# ts5.net
KiCad netlist of a schematic drawn in EAGLE
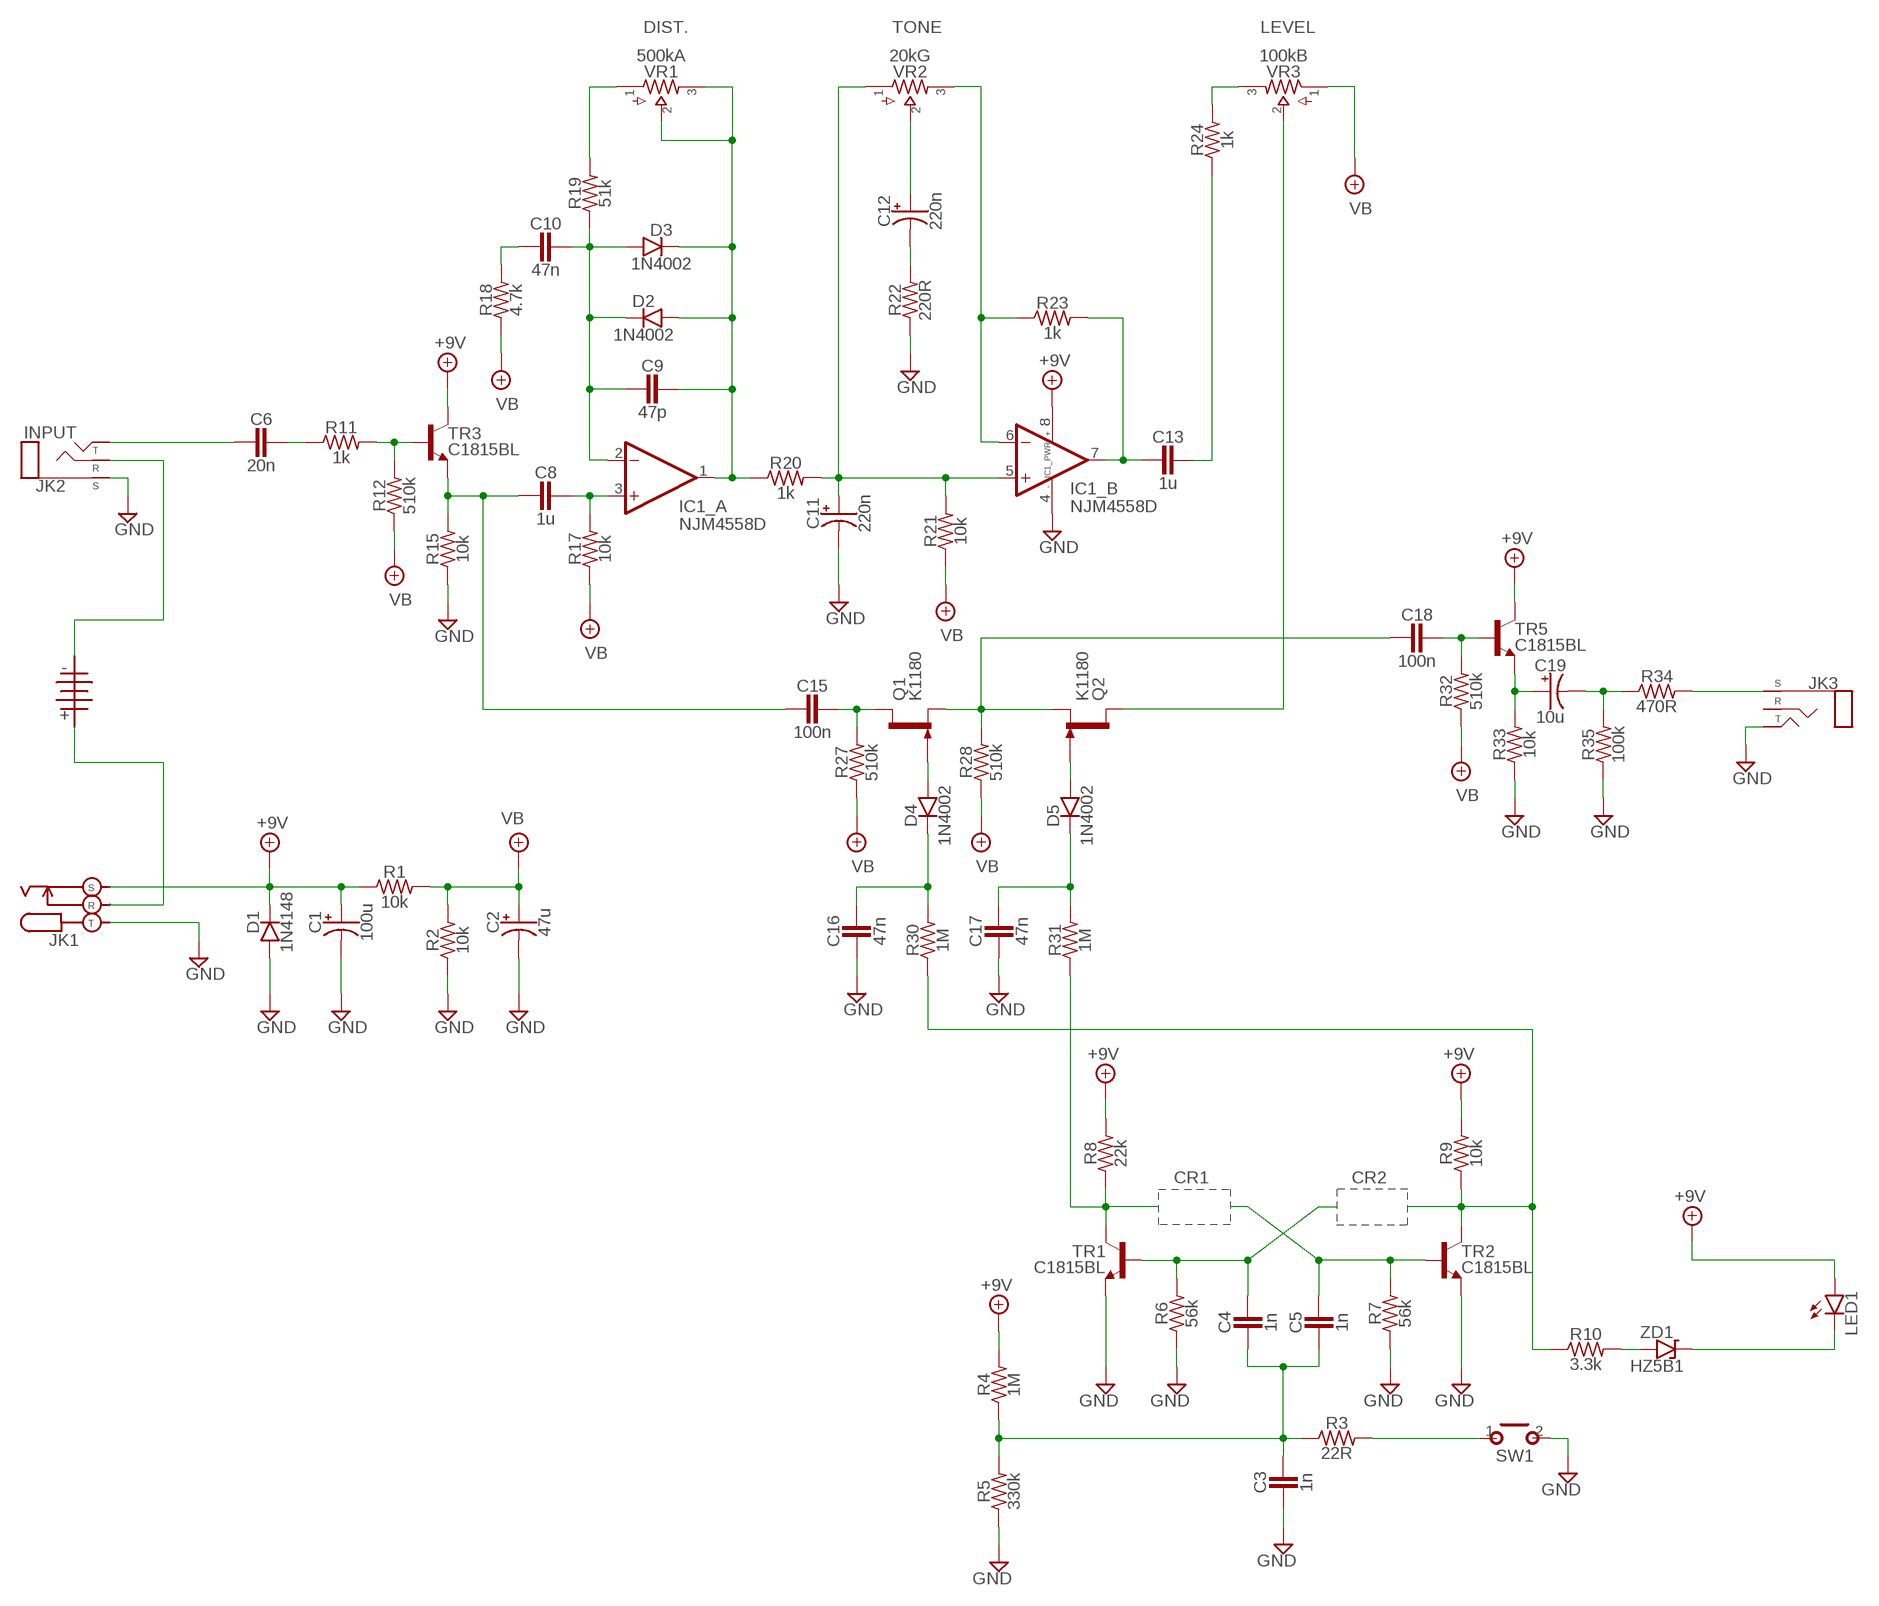
[diagram p0: schematic, sheet 1]

(export (version "E")
  (design (tool "Eeschema 10.0.6"))
  (components
    (comp (ref "1101")
      (value "BATTERY")
      (footprint "eagle-import:TWO_PADS")
      (libsource (lib "eagle-import") (part "BATTERY"))
    )
    (comp (ref "C1")
      (value "100u")
      (footprint "eagle-import:050_020")
      (libsource (lib "eagle-import") (part "0500"))
    )
    (comp (ref "C2")
      (value "47u")
      (footprint "eagle-import:050_020")
      (libsource (lib "eagle-import") (part "0500"))
    )
    (comp (ref "C3")
      (value "1n")
      (footprint "eagle-import:BOX_SMALL")
      (libsource (lib "eagle-import") (part "CER/FILMBOX.1"))
    )
    (comp (ref "C4")
      (value "1n")
      (footprint "eagle-import:BOX_SMALL")
      (libsource (lib "eagle-import") (part "CER/FILMBOX.1"))
    )
    (comp (ref "C5")
      (value "1n")
      (footprint "eagle-import:BOX_SMALL")
      (libsource (lib "eagle-import") (part "CER/FILMBOX.1"))
    )
    (comp (ref "C6")
      (value "20n")
      (footprint "eagle-import:BOX_SMALL")
      (libsource (lib "eagle-import") (part "CER/FILMBOX.1"))
    )
    (comp (ref "C8")
      (value "1u")
      (footprint "eagle-import:BOX_SMALL")
      (libsource (lib "eagle-import") (part "CER/FILMBOX.1"))
    )
    (comp (ref "C9")
      (value "47p")
      (footprint "eagle-import:BOX_SMALL")
      (libsource (lib "eagle-import") (part "CER/FILMBOX.1"))
    )
    (comp (ref "C10")
      (value "47n")
      (footprint "eagle-import:BOX_SMALL")
      (libsource (lib "eagle-import") (part "CER/FILMBOX.1"))
    )
    (comp (ref "C11")
      (value "220n")
      (footprint "eagle-import:050_020")
      (libsource (lib "eagle-import") (part "0500"))
    )
    (comp (ref "C12")
      (value "220n")
      (footprint "eagle-import:050_020")
      (libsource (lib "eagle-import") (part "0500"))
    )
    (comp (ref "C13")
      (value "1u")
      (footprint "eagle-import:BOX_SMALL")
      (libsource (lib "eagle-import") (part "CER/FILMBOX.1"))
    )
    (comp (ref "C15")
      (value "100n")
      (footprint "eagle-import:BOX_SMALL")
      (libsource (lib "eagle-import") (part "CER/FILMBOX.1"))
    )
    (comp (ref "C16")
      (value "47n")
      (footprint "eagle-import:BOX_SMALL")
      (libsource (lib "eagle-import") (part "CER/FILMBOX.1"))
    )
    (comp (ref "C17")
      (value "47n")
      (footprint "eagle-import:BOX_SMALL")
      (libsource (lib "eagle-import") (part "CER/FILMBOX.1"))
    )
    (comp (ref "C18")
      (value "100n")
      (footprint "eagle-import:BOX_SMALL")
      (libsource (lib "eagle-import") (part "CER/FILMBOX.1"))
    )
    (comp (ref "C19")
      (value "10u")
      (footprint "eagle-import:050_020")
      (libsource (lib "eagle-import") (part "0500"))
    )
    (comp (ref "D1")
      (value "1N4148")
      (footprint "eagle-import:DO35-2")
      (libsource (lib "eagle-import") (part "DO35.2"))
    )
    (comp (ref "D2")
      (value "1N4002")
      (footprint "eagle-import:DO35-2")
      (libsource (lib "eagle-import") (part "DO35.2"))
    )
    (comp (ref "D3")
      (value "1N4002")
      (footprint "eagle-import:DO35-2")
      (libsource (lib "eagle-import") (part "DO35.2"))
    )
    (comp (ref "D4")
      (value "1N4002")
      (footprint "eagle-import:DO35-2")
      (libsource (lib "eagle-import") (part "DO35.2"))
    )
    (comp (ref "D5")
      (value "1N4002")
      (footprint "eagle-import:DO35-2")
      (libsource (lib "eagle-import") (part "DO35.2"))
    )
    (comp (ref "IC1")
      (value "NJM4558D")
      (footprint "eagle-import:DIL0")
      (libsource (lib "eagle-import") (part "DUALTH"))
    )
    (comp (ref "JK1")
      (value "DCJACK")
      (footprint "eagle-import:DC_KOBICONN")
      (libsource (lib "eagle-import") (part "DC_KOBICONN"))
    )
    (comp (ref "JK2")
      (value "INPUT")
      (footprint "eagle-import:THREEPADS")
      (libsource (lib "eagle-import") (part "STEREO3PADS"))
    )
    (comp (ref "JK3")
      (value "STEREO")
      (footprint "eagle-import:STEREO_PCB")
      (libsource (lib "eagle-import") (part "STEREO"))
    )
    (comp (ref "LED1")
      (value "TLR124")
      (footprint "eagle-import:3MM_D")
      (libsource (lib "eagle-import") (part "LED"))
    )
    (comp (ref "Q1")
      (value "K1180")
      (footprint "eagle-import:TO92-")
      (libsource (lib "eagle-import") (part "2N5457"))
    )
    (comp (ref "Q2")
      (value "K1180")
      (footprint "eagle-import:TO92-")
      (libsource (lib "eagle-import") (part "2N5457"))
    )
    (comp (ref "R1")
      (value "10k")
      (footprint "eagle-import:R0207_3")
      (libsource (lib "eagle-import") (part "R_.3B"))
    )
    (comp (ref "R2")
      (value "10k")
      (footprint "eagle-import:R0207_3")
      (libsource (lib "eagle-import") (part "R_.3B"))
    )
    (comp (ref "R3")
      (value "22R")
      (footprint "eagle-import:R0207_3")
      (libsource (lib "eagle-import") (part "R_.3B"))
    )
    (comp (ref "R4")
      (value "1M")
      (footprint "eagle-import:R0207_3")
      (libsource (lib "eagle-import") (part "R_.3B"))
    )
    (comp (ref "R5")
      (value "330k")
      (footprint "eagle-import:R0207_3")
      (libsource (lib "eagle-import") (part "R_.3B"))
    )
    (comp (ref "R6")
      (value "56k")
      (footprint "eagle-import:R0207_3")
      (libsource (lib "eagle-import") (part "R_.3B"))
    )
    (comp (ref "R7")
      (value "56k")
      (footprint "eagle-import:R0207_3")
      (libsource (lib "eagle-import") (part "R_.3B"))
    )
    (comp (ref "R8")
      (value "22k")
      (footprint "eagle-import:R0207_3")
      (libsource (lib "eagle-import") (part "R_.3B"))
    )
    (comp (ref "R9")
      (value "10k")
      (footprint "eagle-import:R0207_3")
      (libsource (lib "eagle-import") (part "R_.3B"))
    )
    (comp (ref "R10")
      (value "3.3k")
      (footprint "eagle-import:R0207_3")
      (libsource (lib "eagle-import") (part "R_.3B"))
    )
    (comp (ref "R11")
      (value "1k")
      (footprint "eagle-import:R0207_3")
      (libsource (lib "eagle-import") (part "R_.3B"))
    )
    (comp (ref "R12")
      (value "510k")
      (footprint "eagle-import:R0207_3")
      (libsource (lib "eagle-import") (part "R_.3B"))
    )
    (comp (ref "R15")
      (value "10k")
      (footprint "eagle-import:R0207_3")
      (libsource (lib "eagle-import") (part "R_.3B"))
    )
    (comp (ref "R17")
      (value "10k")
      (footprint "eagle-import:R0207_3")
      (libsource (lib "eagle-import") (part "R_.3B"))
    )
    (comp (ref "R18")
      (value "4.7k")
      (footprint "eagle-import:R0207_3")
      (libsource (lib "eagle-import") (part "R_.3B"))
    )
    (comp (ref "R19")
      (value "51k")
      (footprint "eagle-import:R0207_3")
      (libsource (lib "eagle-import") (part "R_.3B"))
    )
    (comp (ref "R20")
      (value "1k")
      (footprint "eagle-import:R0207_3")
      (libsource (lib "eagle-import") (part "R_.3B"))
    )
    (comp (ref "R21")
      (value "10k")
      (footprint "eagle-import:R0207_3")
      (libsource (lib "eagle-import") (part "R_.3B"))
    )
    (comp (ref "R22")
      (value "220R")
      (footprint "eagle-import:R0207_3")
      (libsource (lib "eagle-import") (part "R_.3B"))
    )
    (comp (ref "R23")
      (value "1k")
      (footprint "eagle-import:R0207_3")
      (libsource (lib "eagle-import") (part "R_.3B"))
    )
    (comp (ref "R24")
      (value "1k")
      (footprint "eagle-import:R0207_3")
      (libsource (lib "eagle-import") (part "R_.3B"))
    )
    (comp (ref "R27")
      (value "510k")
      (footprint "eagle-import:R0207_3")
      (libsource (lib "eagle-import") (part "R_.3B"))
    )
    (comp (ref "R28")
      (value "510k")
      (footprint "eagle-import:R0207_3")
      (libsource (lib "eagle-import") (part "R_.3B"))
    )
    (comp (ref "R30")
      (value "1M")
      (footprint "eagle-import:R0207_3")
      (libsource (lib "eagle-import") (part "R_.3B"))
    )
    (comp (ref "R31")
      (value "1M")
      (footprint "eagle-import:R0207_3")
      (libsource (lib "eagle-import") (part "R_.3B"))
    )
    (comp (ref "R32")
      (value "510k")
      (footprint "eagle-import:R0207_3")
      (libsource (lib "eagle-import") (part "R_.3B"))
    )
    (comp (ref "R33")
      (value "10k")
      (footprint "eagle-import:R0207_3")
      (libsource (lib "eagle-import") (part "R_.3B"))
    )
    (comp (ref "R34")
      (value "470R")
      (footprint "eagle-import:R0207_3")
      (libsource (lib "eagle-import") (part "R_.3B"))
    )
    (comp (ref "R35")
      (value "100k")
      (footprint "eagle-import:R0207_3")
      (libsource (lib "eagle-import") (part "R_.3B"))
    )
    (comp (ref "SW1")
      (value "MOMENTARY")
      (footprint "eagle-import:SPST")
      (libsource (lib "eagle-import") (part "MOMENTARY"))
    )
    (comp (ref "TR1")
      (value "C1815BL")
      (footprint "eagle-import:TO92-")
      (libsource (lib "eagle-import") (part "2SC828A"))
    )
    (comp (ref "TR2")
      (value "C1815BL")
      (footprint "eagle-import:TO92-")
      (libsource (lib "eagle-import") (part "2SC828A"))
    )
    (comp (ref "TR3")
      (value "C1815BL")
      (footprint "eagle-import:TO92-")
      (libsource (lib "eagle-import") (part "2N3904"))
    )
    (comp (ref "TR5")
      (value "C1815BL")
      (footprint "eagle-import:TO92-")
      (libsource (lib "eagle-import") (part "2N3904"))
    )
    (comp (ref "VR1")
      (value "500kA")
      (footprint "eagle-import:16MM")
      (libsource (lib "eagle-import") (part "POTS16MM"))
    )
    (comp (ref "VR2")
      (value "20kG")
      (footprint "eagle-import:16MM")
      (libsource (lib "eagle-import") (part "POTS16MM"))
    )
    (comp (ref "VR3")
      (value "100kB")
      (footprint "eagle-import:16MM")
      (libsource (lib "eagle-import") (part "POTS16MM"))
    )
    (comp (ref "ZD1")
      (value "HZ5B1")
      (footprint "eagle-import:DO41-2")
      (libsource (lib "eagle-import") (part "ZENER.2"))
    )
  )
  (nets
    (net (code "1") (name "+9V") (class "Default")
      (node (ref "C1") (pin "+") (pinfunction "+_+") (pintype "passive"))
      (node (ref "D1") (pin "C") (pinfunction "C_C") (pintype "passive"))
      (node (ref "IC1") (pin "8") (pinfunction "V+_8") (pintype "power_in"))
      (node (ref "JK1") (pin "S") (pinfunction "S_S") (pintype "bidirectional"))
      (node (ref "LED1") (pin "ANODE") (pinfunction "A_ANODE") (pintype "passive"))
      (node (ref "R1") (pin "1") (pinfunction "1_1") (pintype "passive"))
      (node (ref "R4") (pin "2") (pinfunction "2_2") (pintype "passive"))
      (node (ref "R8") (pin "2") (pinfunction "2_2") (pintype "passive"))
      (node (ref "R9") (pin "2") (pinfunction "2_2") (pintype "passive"))
      (node (ref "TR3") (pin "1") (pinfunction "C_1") (pintype "passive"))
      (node (ref "TR5") (pin "1") (pinfunction "C_1") (pintype "passive"))
    )
    (net (code "2") (name "GND") (class "Default")
      (node (ref "C1") (pin "-") (pinfunction "-_-") (pintype "passive"))
      (node (ref "C11") (pin "-") (pinfunction "-_-") (pintype "passive"))
      (node (ref "C16") (pin "2") (pinfunction "2_2") (pintype "passive"))
      (node (ref "C17") (pin "2") (pinfunction "2_2") (pintype "passive"))
      (node (ref "C2") (pin "-") (pinfunction "-_-") (pintype "passive"))
      (node (ref "C3") (pin "2") (pinfunction "2_2") (pintype "passive"))
      (node (ref "D1") (pin "A") (pinfunction "A_A") (pintype "passive"))
      (node (ref "IC1") (pin "4") (pinfunction "V-_4") (pintype "power_in"))
      (node (ref "JK1") (pin "T") (pinfunction "T_T") (pintype "bidirectional"))
      (node (ref "JK2") (pin "SLEEVE") (pinfunction "S_SLEEVE") (pintype "passive"))
      (node (ref "JK3") (pin "P$3") (pinfunction "T_P$3") (pintype "passive"))
      (node (ref "R15") (pin "1") (pinfunction "1_1") (pintype "passive"))
      (node (ref "R2") (pin "1") (pinfunction "1_1") (pintype "passive"))
      (node (ref "R22") (pin "1") (pinfunction "1_1") (pintype "passive"))
      (node (ref "R33") (pin "1") (pinfunction "1_1") (pintype "passive"))
      (node (ref "R35") (pin "1") (pinfunction "1_1") (pintype "passive"))
      (node (ref "R5") (pin "1") (pinfunction "1_1") (pintype "passive"))
      (node (ref "R6") (pin "1") (pinfunction "1_1") (pintype "passive"))
      (node (ref "R7") (pin "1") (pinfunction "1_1") (pintype "passive"))
      (node (ref "SW1") (pin "2") (pinfunction "S_2") (pintype "passive"))
      (node (ref "TR1") (pin "3") (pinfunction "E_3") (pintype "passive"))
      (node (ref "TR2") (pin "3") (pinfunction "E_3") (pintype "passive"))
    )
    (net (code "3") (name "Net-(1101-P$1)") (class "Default")
      (node (ref "1101") (pin "T") (pinfunction "P$1_T") (pintype "bidirectional"))
      (node (ref "JK1") (pin "R") (pinfunction "R_R") (pintype "bidirectional"))
    )
    (net (code "4") (name "Net-(1101-P$2)") (class "Default")
      (node (ref "1101") (pin "S") (pinfunction "P$2_S") (pintype "bidirectional"))
      (node (ref "JK2") (pin "RING") (pinfunction "R_RING") (pintype "passive"))
    )
    (net (code "5") (name "Net-(C3-Pad1)") (class "Default")
      (node (ref "C3") (pin "1") (pinfunction "1_1") (pintype "passive"))
      (node (ref "C4") (pin "2") (pinfunction "2_2") (pintype "passive"))
      (node (ref "C5") (pin "2") (pinfunction "2_2") (pintype "passive"))
      (node (ref "R3") (pin "1") (pinfunction "1_1") (pintype "passive"))
      (node (ref "R4") (pin "1") (pinfunction "1_1") (pintype "passive"))
      (node (ref "R5") (pin "2") (pinfunction "2_2") (pintype "passive"))
    )
    (net (code "6") (name "Net-(C6-Pad1)") (class "Default")
      (node (ref "C6") (pin "1") (pinfunction "1_1") (pintype "passive"))
      (node (ref "R11") (pin "1") (pinfunction "1_1") (pintype "passive"))
    )
    (net (code "7") (name "Net-(C10-Pad2)") (class "Default")
      (node (ref "C10") (pin "2") (pinfunction "2_2") (pintype "passive"))
      (node (ref "R18") (pin "2") (pinfunction "2_2") (pintype "passive"))
    )
    (net (code "8") (name "Net-(C12-Pad+)") (class "Default")
      (node (ref "C12") (pin "+") (pinfunction "+_+") (pintype "passive"))
      (node (ref "VR2") (pin "2") (pinfunction "2_2") (pintype "passive"))
    )
    (net (code "9") (name "Net-(C12-Pad-)") (class "Default")
      (node (ref "C12") (pin "-") (pinfunction "-_-") (pintype "passive"))
      (node (ref "R22") (pin "2") (pinfunction "2_2") (pintype "passive"))
    )
    (net (code "10") (name "Net-(C13-Pad1)") (class "Default")
      (node (ref "C13") (pin "1") (pinfunction "1_1") (pintype "passive"))
      (node (ref "R24") (pin "1") (pinfunction "1_1") (pintype "passive"))
    )
    (net (code "11") (name "Net-(C16-Pad1)") (class "Default")
      (node (ref "C16") (pin "1") (pinfunction "1_1") (pintype "passive"))
      (node (ref "D4") (pin "C") (pinfunction "C_C") (pintype "passive"))
      (node (ref "R30") (pin "2") (pinfunction "2_2") (pintype "passive"))
    )
    (net (code "12") (name "Net-(C17-Pad1)") (class "Default")
      (node (ref "C17") (pin "1") (pinfunction "1_1") (pintype "passive"))
      (node (ref "D5") (pin "C") (pinfunction "C_C") (pintype "passive"))
      (node (ref "R31") (pin "2") (pinfunction "2_2") (pintype "passive"))
    )
    (net (code "13") (name "Net-(C19-Pad-)") (class "Default")
      (node (ref "C19") (pin "-") (pinfunction "-_-") (pintype "passive"))
      (node (ref "R34") (pin "1") (pinfunction "1_1") (pintype "passive"))
      (node (ref "R35") (pin "2") (pinfunction "2_2") (pintype "passive"))
    )
    (net (code "14") (name "Net-(IC1A-+IN)") (class "Default")
      (node (ref "C8") (pin "1") (pinfunction "1_1") (pintype "passive"))
      (node (ref "IC1") (pin "3") (pinfunction "+IN_3") (pintype "input"))
      (node (ref "R17") (pin "2") (pinfunction "2_2") (pintype "passive"))
    )
    (net (code "15") (name "Net-(IC1A--IN)") (class "Default")
      (node (ref "C10") (pin "1") (pinfunction "1_1") (pintype "passive"))
      (node (ref "C9") (pin "2") (pinfunction "2_2") (pintype "passive"))
      (node (ref "D2") (pin "C") (pinfunction "C_C") (pintype "passive"))
      (node (ref "D3") (pin "A") (pinfunction "A_A") (pintype "passive"))
      (node (ref "IC1") (pin "2") (pinfunction "-IN_2") (pintype "input"))
      (node (ref "R19") (pin "1") (pinfunction "1_1") (pintype "passive"))
    )
    (net (code "16") (name "Net-(IC1A-OUT)") (class "Default")
      (node (ref "C9") (pin "1") (pinfunction "1_1") (pintype "passive"))
      (node (ref "D2") (pin "A") (pinfunction "A_A") (pintype "passive"))
      (node (ref "D3") (pin "C") (pinfunction "C_C") (pintype "passive"))
      (node (ref "IC1") (pin "1") (pinfunction "OUT_1") (pintype "output"))
      (node (ref "R20") (pin "1") (pinfunction "1_1") (pintype "passive"))
      (node (ref "VR1") (pin "2") (pinfunction "2_2") (pintype "passive"))
      (node (ref "VR1") (pin "3") (pinfunction "3_3") (pintype "passive"))
    )
    (net (code "17") (name "Net-(IC1B-+IN)") (class "Default")
      (node (ref "C11") (pin "+") (pinfunction "+_+") (pintype "passive"))
      (node (ref "IC1") (pin "5") (pinfunction "+IN_5") (pintype "input"))
      (node (ref "R20") (pin "2") (pinfunction "2_2") (pintype "passive"))
      (node (ref "R21") (pin "2") (pinfunction "2_2") (pintype "passive"))
      (node (ref "VR2") (pin "1") (pinfunction "1_1") (pintype "passive"))
    )
    (net (code "18") (name "Net-(IC1B--IN)") (class "Default")
      (node (ref "IC1") (pin "6") (pinfunction "-IN_6") (pintype "input"))
      (node (ref "R23") (pin "1") (pinfunction "1_1") (pintype "passive"))
      (node (ref "VR2") (pin "3") (pinfunction "3_3") (pintype "passive"))
    )
    (net (code "19") (name "Net-(IC1B-OUT)") (class "Default")
      (node (ref "C13") (pin "2") (pinfunction "2_2") (pintype "passive"))
      (node (ref "IC1") (pin "7") (pinfunction "OUT_7") (pintype "output"))
      (node (ref "R23") (pin "2") (pinfunction "2_2") (pintype "passive"))
    )
    (net (code "20") (name "Net-(JK2-T)") (class "Default")
      (node (ref "C6") (pin "2") (pinfunction "2_2") (pintype "passive"))
      (node (ref "JK2") (pin "TIP") (pinfunction "T_TIP") (pintype "passive"))
    )
    (net (code "21") (name "Net-(JK3-S)") (class "Default")
      (node (ref "JK3") (pin "P$1") (pinfunction "S_P$1") (pintype "passive"))
      (node (ref "R34") (pin "2") (pinfunction "2_2") (pintype "passive"))
    )
    (net (code "22") (name "Net-(LED1-C)") (class "Default")
      (node (ref "LED1") (pin "P$1") (pinfunction "C_P$1") (pintype "passive"))
      (node (ref "ZD1") (pin "C") (pinfunction "C_C") (pintype "passive"))
    )
    (net (code "23") (name "Net-(Q1-D)") (class "Default")
      (node (ref "C15") (pin "1") (pinfunction "1_1") (pintype "passive"))
      (node (ref "Q1") (pin "3") (pinfunction "D_3") (pintype "passive"))
      (node (ref "R27") (pin "2") (pinfunction "2_2") (pintype "passive"))
    )
    (net (code "24") (name "Net-(Q1-G)") (class "Default")
      (node (ref "D4") (pin "A") (pinfunction "A_A") (pintype "passive"))
      (node (ref "Q1") (pin "1") (pinfunction "G_1") (pintype "passive"))
    )
    (net (code "25") (name "Net-(Q1-S)") (class "Default")
      (node (ref "C18") (pin "2") (pinfunction "2_2") (pintype "passive"))
      (node (ref "Q1") (pin "2") (pinfunction "S_2") (pintype "passive"))
      (node (ref "Q2") (pin "2") (pinfunction "S_2") (pintype "passive"))
      (node (ref "R28") (pin "2") (pinfunction "2_2") (pintype "passive"))
    )
    (net (code "26") (name "Net-(Q2-D)") (class "Default")
      (node (ref "Q2") (pin "3") (pinfunction "D_3") (pintype "passive"))
      (node (ref "VR3") (pin "2") (pinfunction "2_2") (pintype "passive"))
    )
    (net (code "27") (name "Net-(Q2-G)") (class "Default")
      (node (ref "D5") (pin "A") (pinfunction "A_A") (pintype "passive"))
      (node (ref "Q2") (pin "1") (pinfunction "G_1") (pintype "passive"))
    )
    (net (code "28") (name "Net-(R10-Pad2)") (class "Default")
      (node (ref "R10") (pin "2") (pinfunction "2_2") (pintype "passive"))
      (node (ref "ZD1") (pin "A") (pinfunction "A_A") (pintype "passive"))
    )
    (net (code "29") (name "Net-(R19-Pad2)") (class "Default")
      (node (ref "R19") (pin "2") (pinfunction "2_2") (pintype "passive"))
      (node (ref "VR1") (pin "1") (pinfunction "1_1") (pintype "passive"))
    )
    (net (code "30") (name "Net-(R24-Pad2)") (class "Default")
      (node (ref "R24") (pin "2") (pinfunction "2_2") (pintype "passive"))
      (node (ref "VR3") (pin "3") (pinfunction "3_3") (pintype "passive"))
    )
    (net (code "31") (name "Net-(SW1-P)") (class "Default")
      (node (ref "R3") (pin "2") (pinfunction "2_2") (pintype "passive"))
      (node (ref "SW1") (pin "1") (pinfunction "P_1") (pintype "passive"))
    )
    (net (code "32") (name "Net-(TR1-B)") (class "Default")
      (node (ref "C4") (pin "1") (pinfunction "1_1") (pintype "passive"))
      (node (ref "R6") (pin "2") (pinfunction "2_2") (pintype "passive"))
      (node (ref "TR1") (pin "1") (pinfunction "B_1") (pintype "passive"))
    )
    (net (code "33") (name "Net-(TR1-C)") (class "Default")
      (node (ref "R31") (pin "1") (pinfunction "1_1") (pintype "passive"))
      (node (ref "R8") (pin "1") (pinfunction "1_1") (pintype "passive"))
      (node (ref "TR1") (pin "2") (pinfunction "C_2") (pintype "passive"))
    )
    (net (code "34") (name "Net-(TR2-B)") (class "Default")
      (node (ref "C5") (pin "1") (pinfunction "1_1") (pintype "passive"))
      (node (ref "R7") (pin "2") (pinfunction "2_2") (pintype "passive"))
      (node (ref "TR2") (pin "1") (pinfunction "B_1") (pintype "passive"))
    )
    (net (code "35") (name "Net-(TR2-C)") (class "Default")
      (node (ref "R10") (pin "1") (pinfunction "1_1") (pintype "passive"))
      (node (ref "R30") (pin "1") (pinfunction "1_1") (pintype "passive"))
      (node (ref "R9") (pin "1") (pinfunction "1_1") (pintype "passive"))
      (node (ref "TR2") (pin "2") (pinfunction "C_2") (pintype "passive"))
    )
    (net (code "36") (name "Net-(TR3-B)") (class "Default")
      (node (ref "R11") (pin "2") (pinfunction "2_2") (pintype "passive"))
      (node (ref "R12") (pin "2") (pinfunction "2_2") (pintype "passive"))
      (node (ref "TR3") (pin "2") (pinfunction "B_2") (pintype "passive"))
    )
    (net (code "37") (name "Net-(TR3-E)") (class "Default")
      (node (ref "C15") (pin "2") (pinfunction "2_2") (pintype "passive"))
      (node (ref "C8") (pin "2") (pinfunction "2_2") (pintype "passive"))
      (node (ref "R15") (pin "2") (pinfunction "2_2") (pintype "passive"))
      (node (ref "TR3") (pin "3") (pinfunction "E_3") (pintype "passive"))
    )
    (net (code "38") (name "Net-(TR5-B)") (class "Default")
      (node (ref "C18") (pin "1") (pinfunction "1_1") (pintype "passive"))
      (node (ref "R32") (pin "2") (pinfunction "2_2") (pintype "passive"))
      (node (ref "TR5") (pin "2") (pinfunction "B_2") (pintype "passive"))
    )
    (net (code "39") (name "Net-(TR5-E)") (class "Default")
      (node (ref "C19") (pin "+") (pinfunction "+_+") (pintype "passive"))
      (node (ref "R33") (pin "2") (pinfunction "2_2") (pintype "passive"))
      (node (ref "TR5") (pin "3") (pinfunction "E_3") (pintype "passive"))
    )
    (net (code "40") (name "VB") (class "Default")
      (node (ref "C2") (pin "+") (pinfunction "+_+") (pintype "passive"))
      (node (ref "R1") (pin "2") (pinfunction "2_2") (pintype "passive"))
      (node (ref "R12") (pin "1") (pinfunction "1_1") (pintype "passive"))
      (node (ref "R17") (pin "1") (pinfunction "1_1") (pintype "passive"))
      (node (ref "R18") (pin "1") (pinfunction "1_1") (pintype "passive"))
      (node (ref "R2") (pin "2") (pinfunction "2_2") (pintype "passive"))
      (node (ref "R21") (pin "1") (pinfunction "1_1") (pintype "passive"))
      (node (ref "R27") (pin "1") (pinfunction "1_1") (pintype "passive"))
      (node (ref "R28") (pin "1") (pinfunction "1_1") (pintype "passive"))
      (node (ref "R32") (pin "1") (pinfunction "1_1") (pintype "passive"))
      (node (ref "VR3") (pin "1") (pinfunction "1_1") (pintype "passive"))
    )
    (net (code "41") (name "unconnected-(JK3-R-PadP$2)") (class "Default")
      (node (ref "JK3") (pin "P$2") (pinfunction "R_P$2") (pintype "passive"))
    )
  )
)
